# ADC_BOARD_V1.net
KiCad netlist of a schematic drawn in EAGLE
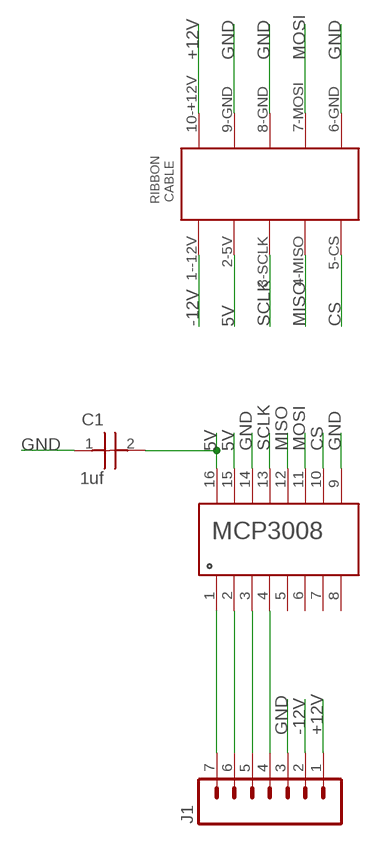
[diagram p0: schematic, sheet 1]

(export (version "E")
  (design (tool "Eeschema 10.0.6"))
  (components
    (comp (ref "C1")
      (value "1uf")
      (footprint "eagle-import:CAP1206")
      (fields (field (name "MPN") "C1206C103K5RACTU") (field (name "TOLERANCE") "±10%"))
      (libsource (lib "eagle-import") (part "CAP1206"))
    )
    (comp (ref "J1")
      (value "M07")
      (footprint "eagle-import:1X07")
      (libsource (lib "eagle-import") (part "M07"))
    )
    (comp (ref "U$1")
      (value "5X2RIBBONCONNECTOR")
      (footprint "eagle-import:5X2RIBBONCONNECTOR")
      (libsource (lib "eagle-import") (part "5X2RIBBONCONNECTOR"))
    )
    (comp (ref "U$2")
      (value "MCP3008-SOIC16")
      (footprint "eagle-import:SOIC16N")
      (libsource (lib "eagle-import") (part "MCP3008-SOIC16"))
    )
  )
  (nets
    (net (code "1") (name "/+12V") (class "Default")
      (node (ref "J1") (pin "1") (pinfunction "1_1") (pintype "passive"))
      (node (ref "U$1") (pin "10-+12V") (pinfunction "10-+12V_10-+12V") (pintype "bidirectional"))
    )
    (net (code "2") (name "/-12V") (class "Default")
      (node (ref "J1") (pin "2") (pinfunction "2_2") (pintype "passive"))
      (node (ref "U$1") (pin "1--12V") (pinfunction "1--12V_1--12V") (pintype "bidirectional"))
    )
    (net (code "3") (name "/5V") (class "Default")
      (node (ref "C1") (pin "2") (pinfunction "P$2_2") (pintype "bidirectional"))
      (node (ref "U$1") (pin "2-5V") (pinfunction "2-5V_2-5V") (pintype "bidirectional"))
      (node (ref "U$2") (pin "15") (pinfunction "15-VREF_15") (pintype "bidirectional"))
      (node (ref "U$2") (pin "16") (pinfunction "16-VDD_16") (pintype "bidirectional"))
    )
    (net (code "4") (name "/CS") (class "Default")
      (node (ref "U$1") (pin "5-CS") (pinfunction "5-CS_5-CS") (pintype "bidirectional"))
      (node (ref "U$2") (pin "10") (pinfunction "10-CS_10") (pintype "bidirectional"))
    )
    (net (code "5") (name "/GND") (class "Default")
      (node (ref "C1") (pin "1") (pinfunction "P$1_1") (pintype "bidirectional"))
      (node (ref "J1") (pin "3") (pinfunction "3_3") (pintype "passive"))
      (node (ref "U$1") (pin "6-GND") (pinfunction "6-GND_6-GND") (pintype "bidirectional"))
      (node (ref "U$1") (pin "8-GND") (pinfunction "8-GND_8-GND") (pintype "bidirectional"))
      (node (ref "U$1") (pin "9-GND") (pinfunction "9-GND_9-GND") (pintype "bidirectional"))
      (node (ref "U$2") (pin "14") (pinfunction "14-AGND_14") (pintype "bidirectional"))
      (node (ref "U$2") (pin "9") (pinfunction "9-DGND_9") (pintype "bidirectional"))
    )
    (net (code "6") (name "/MISO") (class "Default")
      (node (ref "U$1") (pin "4-MISO") (pinfunction "4-MISO_4-MISO") (pintype "bidirectional"))
      (node (ref "U$2") (pin "12") (pinfunction "12-DOUT_12") (pintype "bidirectional"))
    )
    (net (code "7") (name "/MOSI") (class "Default")
      (node (ref "U$1") (pin "7-MOSI") (pinfunction "7-MOSI_7-MOSI") (pintype "bidirectional"))
      (node (ref "U$2") (pin "11") (pinfunction "11-DIN_11") (pintype "bidirectional"))
    )
    (net (code "8") (name "/SCLK") (class "Default")
      (node (ref "U$1") (pin "3-SCLK") (pinfunction "3-SCLK_3-SCLK") (pintype "bidirectional"))
      (node (ref "U$2") (pin "13") (pinfunction "13-CLK_13") (pintype "bidirectional"))
    )
    (net (code "9") (name "Net-(U$2-1-CH0)") (class "Default")
      (node (ref "J1") (pin "7") (pinfunction "7_7") (pintype "passive"))
      (node (ref "U$2") (pin "1") (pinfunction "1-CH0_1") (pintype "bidirectional"))
    )
    (net (code "10") (name "Net-(U$2-2-CH1)") (class "Default")
      (node (ref "J1") (pin "6") (pinfunction "6_6") (pintype "passive"))
      (node (ref "U$2") (pin "2") (pinfunction "2-CH1_2") (pintype "bidirectional"))
    )
    (net (code "11") (name "Net-(U$2-3-CH2)") (class "Default")
      (node (ref "J1") (pin "5") (pinfunction "5_5") (pintype "passive"))
      (node (ref "U$2") (pin "3") (pinfunction "3-CH2_3") (pintype "bidirectional"))
    )
    (net (code "12") (name "Net-(U$2-4-CH3)") (class "Default")
      (node (ref "J1") (pin "4") (pinfunction "4_4") (pintype "passive"))
      (node (ref "U$2") (pin "4") (pinfunction "4-CH3_4") (pintype "bidirectional"))
    )
    (net (code "13") (name "unconnected-(U$2-5-CH4-Pad5)") (class "Default")
      (node (ref "U$2") (pin "5") (pinfunction "5-CH4_5") (pintype "bidirectional"))
    )
    (net (code "14") (name "unconnected-(U$2-6-CH5-Pad6)") (class "Default")
      (node (ref "U$2") (pin "6") (pinfunction "6-CH5_6") (pintype "bidirectional"))
    )
    (net (code "15") (name "unconnected-(U$2-7-CH6-Pad7)") (class "Default")
      (node (ref "U$2") (pin "7") (pinfunction "7-CH6_7") (pintype "bidirectional"))
    )
    (net (code "16") (name "unconnected-(U$2-8-CH7-Pad8)") (class "Default")
      (node (ref "U$2") (pin "8") (pinfunction "8-CH7_8") (pintype "bidirectional"))
    )
  )
)
